# 4_Stepper_motor_control_board.net
KiCad netlist of a schematic drawn in EAGLE
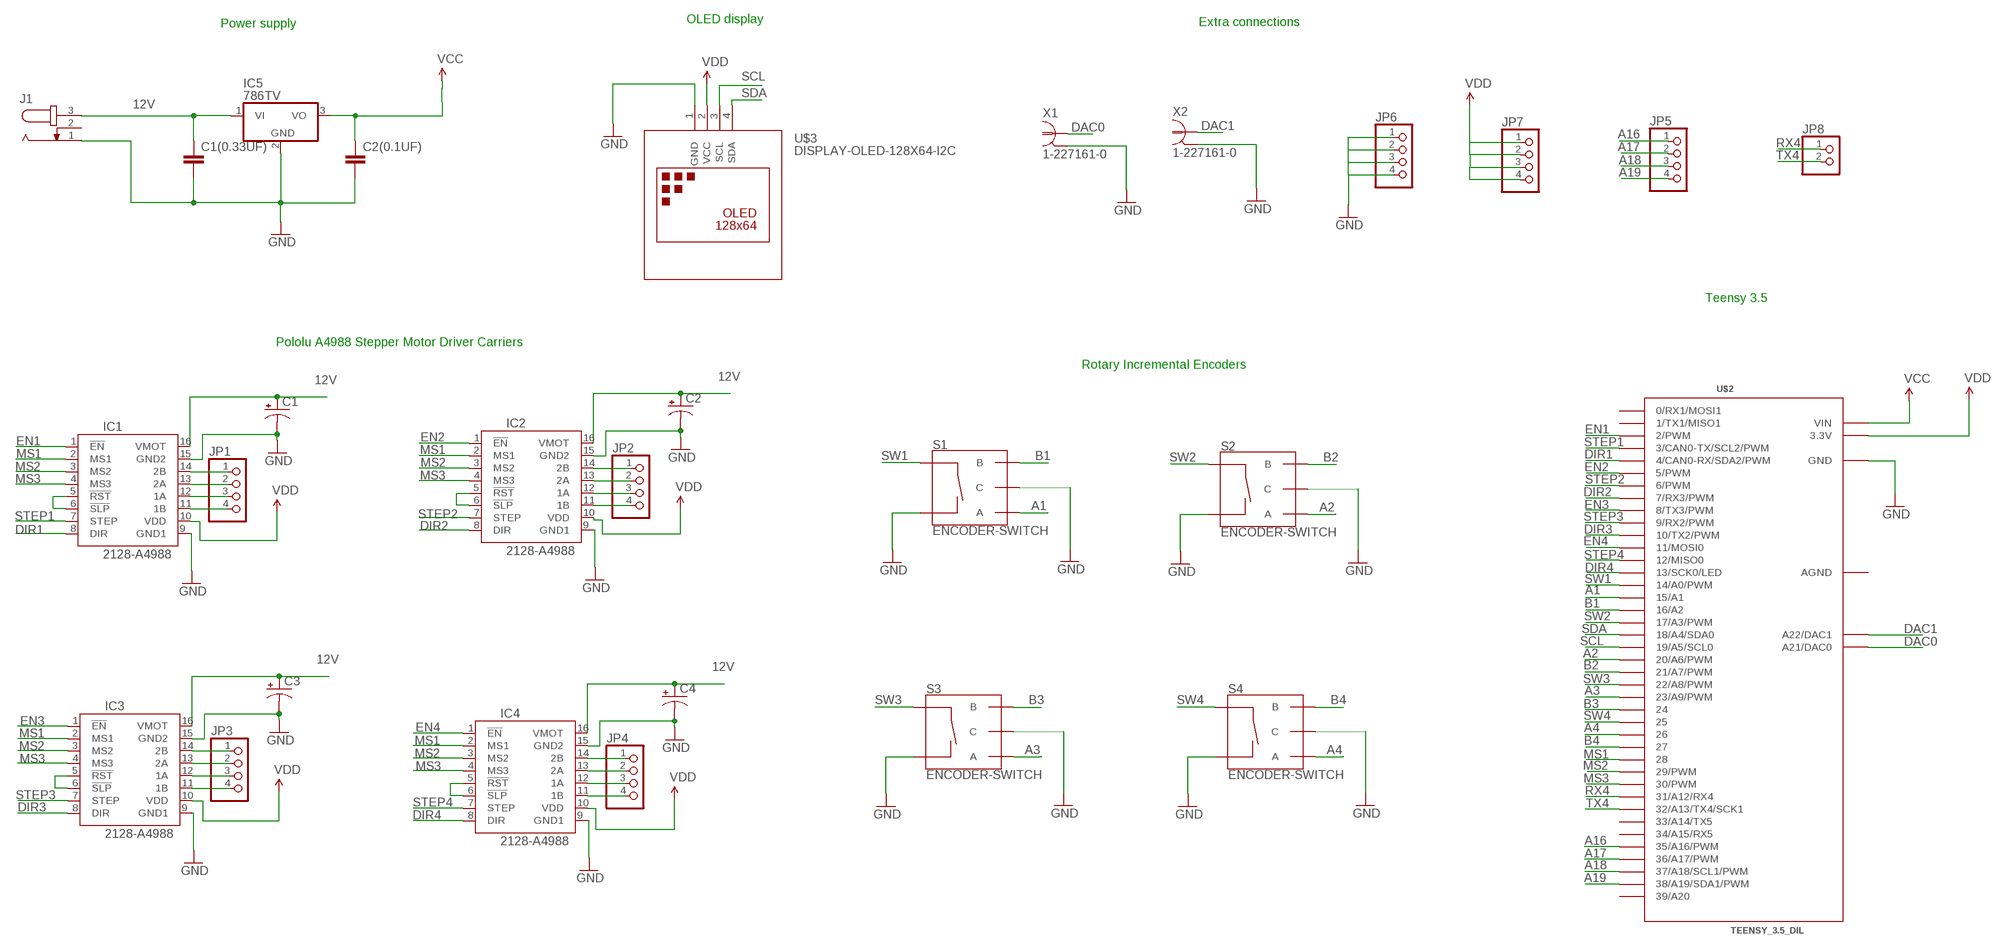
[diagram p0: schematic, sheet 1]

(export (version "E")
  (design (tool "Eeschema 10.0.6"))
  (components
    (comp (ref "C1")
      (value "CPOL-USE5-5")
      (footprint "eagle-import:E5-5")
      (libsource (lib "eagle-import") (part "CPOL-USE5-5"))
    )
    (comp (ref "C1(0.33UF)")
      (value "C2.5/4")
      (footprint "eagle-import:C2.5-4")
      (libsource (lib "eagle-import") (part "C2.5/4"))
    )
    (comp (ref "C2")
      (value "CPOL-USE5-5")
      (footprint "eagle-import:E5-5")
      (libsource (lib "eagle-import") (part "CPOL-USE5-5"))
    )
    (comp (ref "C2(0.1UF)")
      (value "C2.5/2")
      (footprint "eagle-import:C2.5-2")
      (libsource (lib "eagle-import") (part "C2.5/2"))
    )
    (comp (ref "C3")
      (value "CPOL-USE5-5")
      (footprint "eagle-import:E5-5")
      (libsource (lib "eagle-import") (part "CPOL-USE5-5"))
    )
    (comp (ref "C4")
      (value "CPOL-USE5-5")
      (footprint "eagle-import:E5-5")
      (libsource (lib "eagle-import") (part "CPOL-USE5-5"))
    )
    (comp (ref "IC1")
      (value "2128-A4988")
      (footprint "eagle-import:A4988")
      (libsource (lib "eagle-import") (part "2128-A4988"))
    )
    (comp (ref "IC2")
      (value "2128-A4988")
      (footprint "eagle-import:A4988")
      (libsource (lib "eagle-import") (part "2128-A4988"))
    )
    (comp (ref "IC3")
      (value "2128-A4988")
      (footprint "eagle-import:A4988")
      (libsource (lib "eagle-import") (part "2128-A4988"))
    )
    (comp (ref "IC4")
      (value "2128-A4988")
      (footprint "eagle-import:A4988")
      (libsource (lib "eagle-import") (part "2128-A4988"))
    )
    (comp (ref "IC5")
      (value "786TV")
      (footprint "eagle-import:TO220V")
      (libsource (lib "eagle-import") (part "78TV6"))
    )
    (comp (ref "J1")
      (value "JACK-PLUG0")
      (footprint "eagle-import:SPC4077")
      (libsource (lib "eagle-import") (part "JACK-PLUG0"))
    )
    (comp (ref "JP1")
      (value "PINHD-1X4")
      (footprint "eagle-import:1X04")
      (libsource (lib "eagle-import") (part "PINHD-1X4"))
    )
    (comp (ref "JP2")
      (value "PINHD-1X4")
      (footprint "eagle-import:1X04")
      (libsource (lib "eagle-import") (part "PINHD-1X4"))
    )
    (comp (ref "JP3")
      (value "PINHD-1X4")
      (footprint "eagle-import:1X04")
      (libsource (lib "eagle-import") (part "PINHD-1X4"))
    )
    (comp (ref "JP4")
      (value "PINHD-1X4")
      (footprint "eagle-import:1X04")
      (libsource (lib "eagle-import") (part "PINHD-1X4"))
    )
    (comp (ref "JP5")
      (value "PINHD-1X4")
      (footprint "eagle-import:1X04")
      (libsource (lib "eagle-import") (part "PINHD-1X4"))
    )
    (comp (ref "JP6")
      (value "PINHD-1X4")
      (footprint "eagle-import:1X04")
      (libsource (lib "eagle-import") (part "PINHD-1X4"))
    )
    (comp (ref "JP7")
      (value "PINHD-1X4")
      (footprint "eagle-import:1X04")
      (libsource (lib "eagle-import") (part "PINHD-1X4"))
    )
    (comp (ref "JP8")
      (value "PINHD-1X2")
      (footprint "eagle-import:1X02")
      (libsource (lib "eagle-import") (part "PINHD-1X2"))
    )
    (comp (ref "S1")
      (value "ENCODER-SWITCH")
      (footprint "eagle-import:ROTARY_ENC_PLAIN")
      (libsource (lib "eagle-import") (part "ENCODER-SWITCH"))
    )
    (comp (ref "S2")
      (value "ENCODER-SWITCH")
      (footprint "eagle-import:ROTARY_ENC_PLAIN")
      (libsource (lib "eagle-import") (part "ENCODER-SWITCH"))
    )
    (comp (ref "S3")
      (value "ENCODER-SWITCH")
      (footprint "eagle-import:ROTARY_ENC_PLAIN")
      (libsource (lib "eagle-import") (part "ENCODER-SWITCH"))
    )
    (comp (ref "S4")
      (value "ENCODER-SWITCH")
      (footprint "eagle-import:ROTARY_ENC_PLAIN")
      (libsource (lib "eagle-import") (part "ENCODER-SWITCH"))
    )
    (comp (ref "U$2")
      (value "TEENSY_3.5_DIL")
      (footprint "eagle-import:TEENSY_3.5_DIL")
      (libsource (lib "eagle-import") (part "TEENSY_3.5_DIL"))
    )
    (comp (ref "U$3")
      (value "DISPLAY-OLED-128X64-I2C")
      (footprint "eagle-import:DISPLAY-OLED-128X64-I2C")
      (libsource (lib "eagle-import") (part "DISPLAY-OLED-128X64-I2C"))
    )
    (comp (ref "X1")
      (value "1-227161-0")
      (footprint "eagle-import:AMP_227161")
      (fields (field (name "MF") "TYCO ELECTRONICS") (field (name "MPN") "1-227161"))
      (libsource (lib "eagle-import") (part "?2271611--0"))
    )
    (comp (ref "X2")
      (value "1-227161-0")
      (footprint "eagle-import:AMP_227161")
      (fields (field (name "MF") "TYCO ELECTRONICS") (field (name "MPN") "1-227161"))
      (libsource (lib "eagle-import") (part "?2271611--0"))
    )
  )
  (nets
    (net (code "1") (name "/12V") (class "Default")
      (node (ref "C1") (pin "+") (pinfunction "+_+") (pintype "passive"))
      (node (ref "C1(0.33UF)") (pin "1") (pinfunction "1_1") (pintype "passive"))
      (node (ref "C2") (pin "+") (pinfunction "+_+") (pintype "passive"))
      (node (ref "C3") (pin "+") (pinfunction "+_+") (pintype "passive"))
      (node (ref "C4") (pin "+") (pinfunction "+_+") (pintype "passive"))
      (node (ref "IC1") (pin "16") (pinfunction "VMOT_16") (pintype "power_in"))
      (node (ref "IC2") (pin "16") (pinfunction "VMOT_16") (pintype "power_in"))
      (node (ref "IC3") (pin "16") (pinfunction "VMOT_16") (pintype "power_in"))
      (node (ref "IC4") (pin "16") (pinfunction "VMOT_16") (pintype "power_in"))
      (node (ref "IC5") (pin "1") (pinfunction "VI_1") (pintype "input"))
      (node (ref "J1") (pin "3") (pinfunction "3_3") (pintype "passive"))
    )
    (net (code "2") (name "/A1") (class "Default")
      (node (ref "S1") (pin "A") (pinfunction "A_A") (pintype "bidirectional"))
      (node (ref "U$2") (pin "15/A1") (pinfunction "15/A1_15/A1") (pintype "bidirectional"))
    )
    (net (code "3") (name "/A2") (class "Default")
      (node (ref "S2") (pin "A") (pinfunction "A_A") (pintype "bidirectional"))
      (node (ref "U$2") (pin "20/A6") (pinfunction "20/A6/PWM_20/A6") (pintype "bidirectional"))
    )
    (net (code "4") (name "/A3") (class "Default")
      (node (ref "S3") (pin "A") (pinfunction "A_A") (pintype "bidirectional"))
      (node (ref "U$2") (pin "23/A9") (pinfunction "23/A9/PWM_23/A9") (pintype "bidirectional"))
    )
    (net (code "5") (name "/A4") (class "Default")
      (node (ref "S4") (pin "A") (pinfunction "A_A") (pintype "bidirectional"))
      (node (ref "U$2") (pin "26") (pinfunction "26_26") (pintype "bidirectional"))
    )
    (net (code "6") (name "/A16") (class "Default")
      (node (ref "JP5") (pin "1") (pinfunction "1_1") (pintype "passive"))
      (node (ref "U$2") (pin "35/A16") (pinfunction "35/A16/PWM_35/A16") (pintype "bidirectional"))
    )
    (net (code "7") (name "/A17") (class "Default")
      (node (ref "JP5") (pin "2") (pinfunction "2_2") (pintype "passive"))
      (node (ref "U$2") (pin "36/A17") (pinfunction "36/A17/PWM_36/A17") (pintype "bidirectional"))
    )
    (net (code "8") (name "/A18") (class "Default")
      (node (ref "JP5") (pin "3") (pinfunction "3_3") (pintype "passive"))
      (node (ref "U$2") (pin "37/A18") (pinfunction "37/A18/SCL1/PWM_37/A18") (pintype "bidirectional"))
    )
    (net (code "9") (name "/A19") (class "Default")
      (node (ref "JP5") (pin "4") (pinfunction "4_4") (pintype "passive"))
      (node (ref "U$2") (pin "38/A19") (pinfunction "38/A19/SDA1/PWM_38/A19") (pintype "bidirectional"))
    )
    (net (code "10") (name "/AGND") (class "Default")
      (node (ref "U$2") (pin "AGND") (pinfunction "AGND_AGND") (pintype "power_in"))
    )
    (net (code "11") (name "/B1") (class "Default")
      (node (ref "S1") (pin "B") (pinfunction "B_B") (pintype "bidirectional"))
      (node (ref "U$2") (pin "16/A2") (pinfunction "16/A2_16/A2") (pintype "bidirectional"))
    )
    (net (code "12") (name "/B2") (class "Default")
      (node (ref "S2") (pin "B") (pinfunction "B_B") (pintype "bidirectional"))
      (node (ref "U$2") (pin "21/A7") (pinfunction "21/A7/PWM_21/A7") (pintype "bidirectional"))
    )
    (net (code "13") (name "/B3") (class "Default")
      (node (ref "S3") (pin "B") (pinfunction "B_B") (pintype "bidirectional"))
      (node (ref "U$2") (pin "24") (pinfunction "24_24") (pintype "bidirectional"))
    )
    (net (code "14") (name "/B4") (class "Default")
      (node (ref "S4") (pin "B") (pinfunction "B_B") (pintype "bidirectional"))
      (node (ref "U$2") (pin "27") (pinfunction "27_27") (pintype "bidirectional"))
    )
    (net (code "15") (name "/DAC0") (class "Default")
      (node (ref "U$2") (pin "A21") (pinfunction "A21/DAC0_A21") (pintype "bidirectional"))
      (node (ref "X1") (pin "1") (pinfunction "1_1") (pintype "passive"))
    )
    (net (code "16") (name "/DAC1") (class "Default")
      (node (ref "U$2") (pin "A22") (pinfunction "A22/DAC1_A22") (pintype "bidirectional"))
      (node (ref "X2") (pin "1") (pinfunction "1_1") (pintype "passive"))
    )
    (net (code "17") (name "/DIR1") (class "Default")
      (node (ref "IC1") (pin "8") (pinfunction "DIR_8") (pintype "input"))
      (node (ref "U$2") (pin "4") (pinfunction "4/CAN0-RX/SDA2/PWM_4") (pintype "bidirectional"))
    )
    (net (code "18") (name "/DIR2") (class "Default")
      (node (ref "IC2") (pin "8") (pinfunction "DIR_8") (pintype "input"))
      (node (ref "U$2") (pin "7") (pinfunction "7/RX3/PWM_7") (pintype "bidirectional"))
    )
    (net (code "19") (name "/DIR3") (class "Default")
      (node (ref "IC3") (pin "8") (pinfunction "DIR_8") (pintype "input"))
      (node (ref "U$2") (pin "10") (pinfunction "10/TX2/PWM_10") (pintype "bidirectional"))
    )
    (net (code "20") (name "/DIR4") (class "Default")
      (node (ref "IC4") (pin "8") (pinfunction "DIR_8") (pintype "input"))
      (node (ref "U$2") (pin "13") (pinfunction "13/SCK0/LED_13") (pintype "bidirectional"))
    )
    (net (code "21") (name "/EN1") (class "Default")
      (node (ref "IC1") (pin "1") (pinfunction "~{EN}_1") (pintype "passive"))
      (node (ref "U$2") (pin "2") (pinfunction "2/PWM_2") (pintype "bidirectional"))
    )
    (net (code "22") (name "/EN2") (class "Default")
      (node (ref "IC2") (pin "1") (pinfunction "~{EN}_1") (pintype "passive"))
      (node (ref "U$2") (pin "5") (pinfunction "5/PWM_5") (pintype "bidirectional"))
    )
    (net (code "23") (name "/EN3") (class "Default")
      (node (ref "IC3") (pin "1") (pinfunction "~{EN}_1") (pintype "passive"))
      (node (ref "U$2") (pin "8") (pinfunction "8/TX3/PWM_8") (pintype "bidirectional"))
    )
    (net (code "24") (name "/EN4") (class "Default")
      (node (ref "IC4") (pin "1") (pinfunction "~{EN}_1") (pintype "passive"))
      (node (ref "U$2") (pin "11") (pinfunction "11/MOSI0_11") (pintype "bidirectional"))
    )
    (net (code "25") (name "/MS1") (class "Default")
      (node (ref "IC1") (pin "2") (pinfunction "MS1_2") (pintype "passive"))
      (node (ref "IC2") (pin "2") (pinfunction "MS1_2") (pintype "passive"))
      (node (ref "IC3") (pin "2") (pinfunction "MS1_2") (pintype "passive"))
      (node (ref "IC4") (pin "2") (pinfunction "MS1_2") (pintype "passive"))
      (node (ref "U$2") (pin "28") (pinfunction "28_28") (pintype "bidirectional"))
    )
    (net (code "26") (name "/MS2") (class "Default")
      (node (ref "IC1") (pin "3") (pinfunction "MS2_3") (pintype "passive"))
      (node (ref "IC2") (pin "3") (pinfunction "MS2_3") (pintype "passive"))
      (node (ref "IC3") (pin "3") (pinfunction "MS2_3") (pintype "passive"))
      (node (ref "IC4") (pin "3") (pinfunction "MS2_3") (pintype "passive"))
      (node (ref "U$2") (pin "29") (pinfunction "29/PWM_29") (pintype "bidirectional"))
    )
    (net (code "27") (name "/MS3") (class "Default")
      (node (ref "IC1") (pin "4") (pinfunction "MS3_4") (pintype "passive"))
      (node (ref "IC2") (pin "4") (pinfunction "MS3_4") (pintype "passive"))
      (node (ref "IC3") (pin "4") (pinfunction "MS3_4") (pintype "passive"))
      (node (ref "IC4") (pin "4") (pinfunction "MS3_4") (pintype "passive"))
      (node (ref "U$2") (pin "30") (pinfunction "30/PWM_30") (pintype "bidirectional"))
    )
    (net (code "28") (name "/RX4") (class "Default")
      (node (ref "JP8") (pin "1") (pinfunction "1_1") (pintype "passive"))
      (node (ref "U$2") (pin "31/A12") (pinfunction "31/A12/RX4_31/A12") (pintype "bidirectional"))
    )
    (net (code "29") (name "/SCL") (class "Default")
      (node (ref "U$2") (pin "19/A5") (pinfunction "19/A5/SCL0_19/A5") (pintype "bidirectional"))
      (node (ref "U$3") (pin "3") (pinfunction "SCL_3") (pintype "bidirectional"))
    )
    (net (code "30") (name "/SDA") (class "Default")
      (node (ref "U$2") (pin "18/A4") (pinfunction "18/A4/SDA0_18/A4") (pintype "bidirectional"))
      (node (ref "U$3") (pin "4") (pinfunction "SDA_4") (pintype "bidirectional"))
    )
    (net (code "31") (name "/STEP1") (class "Default")
      (node (ref "IC1") (pin "7") (pinfunction "STEP_7") (pintype "input"))
      (node (ref "U$2") (pin "3") (pinfunction "3/CAN0-TX/SCL2/PWM_3") (pintype "bidirectional"))
    )
    (net (code "32") (name "/STEP2") (class "Default")
      (node (ref "IC2") (pin "7") (pinfunction "STEP_7") (pintype "input"))
      (node (ref "U$2") (pin "6") (pinfunction "6/PWM_6") (pintype "bidirectional"))
    )
    (net (code "33") (name "/STEP3") (class "Default")
      (node (ref "IC3") (pin "7") (pinfunction "STEP_7") (pintype "input"))
      (node (ref "U$2") (pin "9") (pinfunction "9/RX2/PWM_9") (pintype "bidirectional"))
    )
    (net (code "34") (name "/STEP4") (class "Default")
      (node (ref "IC4") (pin "7") (pinfunction "STEP_7") (pintype "input"))
      (node (ref "U$2") (pin "12") (pinfunction "12/MISO0_12") (pintype "bidirectional"))
    )
    (net (code "35") (name "/SW1") (class "Default")
      (node (ref "S1") (pin "SW+") (pinfunction "SW+_SW+") (pintype "bidirectional"))
      (node (ref "U$2") (pin "14/A0") (pinfunction "14/A0/PWM_14/A0") (pintype "bidirectional"))
    )
    (net (code "36") (name "/SW2") (class "Default")
      (node (ref "S2") (pin "SW+") (pinfunction "SW+_SW+") (pintype "bidirectional"))
      (node (ref "U$2") (pin "17/A3") (pinfunction "17/A3/PWM_17/A3") (pintype "bidirectional"))
    )
    (net (code "37") (name "/SW3") (class "Default")
      (node (ref "S3") (pin "SW+") (pinfunction "SW+_SW+") (pintype "bidirectional"))
      (node (ref "U$2") (pin "22/A8") (pinfunction "22/A8/PWM_22/A8") (pintype "bidirectional"))
    )
    (net (code "38") (name "/SW4") (class "Default")
      (node (ref "S4") (pin "SW+") (pinfunction "SW+_SW+") (pintype "bidirectional"))
      (node (ref "U$2") (pin "25") (pinfunction "25_25") (pintype "bidirectional"))
    )
    (net (code "39") (name "/TX4") (class "Default")
      (node (ref "JP8") (pin "2") (pinfunction "2_2") (pintype "passive"))
      (node (ref "U$2") (pin "32/A13") (pinfunction "32/A13/TX4/SCK1_32/A13") (pintype "bidirectional"))
    )
    (net (code "40") (name "GND") (class "Default")
      (node (ref "C1") (pin "-") (pinfunction "-_-") (pintype "passive"))
      (node (ref "C1(0.33UF)") (pin "2") (pinfunction "2_2") (pintype "passive"))
      (node (ref "C2") (pin "-") (pinfunction "-_-") (pintype "passive"))
      (node (ref "C2(0.1UF)") (pin "2") (pinfunction "2_2") (pintype "passive"))
      (node (ref "C3") (pin "-") (pinfunction "-_-") (pintype "passive"))
      (node (ref "C4") (pin "-") (pinfunction "-_-") (pintype "passive"))
      (node (ref "IC1") (pin "15") (pinfunction "GND2_15") (pintype "power_in"))
      (node (ref "IC1") (pin "9") (pinfunction "GND1_9") (pintype "power_in"))
      (node (ref "IC2") (pin "15") (pinfunction "GND2_15") (pintype "power_in"))
      (node (ref "IC2") (pin "9") (pinfunction "GND1_9") (pintype "power_in"))
      (node (ref "IC3") (pin "15") (pinfunction "GND2_15") (pintype "power_in"))
      (node (ref "IC3") (pin "9") (pinfunction "GND1_9") (pintype "power_in"))
      (node (ref "IC4") (pin "15") (pinfunction "GND2_15") (pintype "power_in"))
      (node (ref "IC4") (pin "9") (pinfunction "GND1_9") (pintype "power_in"))
      (node (ref "IC5") (pin "2") (pinfunction "GND_2") (pintype "passive"))
      (node (ref "J1") (pin "1") (pinfunction "1_1") (pintype "passive"))
      (node (ref "JP6") (pin "1") (pinfunction "1_1") (pintype "passive"))
      (node (ref "JP6") (pin "2") (pinfunction "2_2") (pintype "passive"))
      (node (ref "JP6") (pin "3") (pinfunction "3_3") (pintype "passive"))
      (node (ref "JP6") (pin "4") (pinfunction "4_4") (pintype "passive"))
      (node (ref "S1") (pin "C") (pinfunction "C_C") (pintype "bidirectional"))
      (node (ref "S1") (pin "SW-") (pinfunction "SW-_SW-") (pintype "bidirectional"))
      (node (ref "S2") (pin "C") (pinfunction "C_C") (pintype "bidirectional"))
      (node (ref "S2") (pin "SW-") (pinfunction "SW-_SW-") (pintype "bidirectional"))
      (node (ref "S3") (pin "C") (pinfunction "C_C") (pintype "bidirectional"))
      (node (ref "S3") (pin "SW-") (pinfunction "SW-_SW-") (pintype "bidirectional"))
      (node (ref "S4") (pin "C") (pinfunction "C_C") (pintype "bidirectional"))
      (node (ref "S4") (pin "SW-") (pinfunction "SW-_SW-") (pintype "bidirectional"))
      (node (ref "U$2") (pin "GND") (pinfunction "GND_GND") (pintype "power_in"))
      (node (ref "U$2") (pin "GND1") (pinfunction "GND_GND1") (pintype "power_in"))
      (node (ref "U$3") (pin "1") (pinfunction "GND_1") (pintype "power_in"))
      (node (ref "X1") (pin "2") (pinfunction "2_2") (pintype "passive"))
      (node (ref "X2") (pin "2") (pinfunction "2_2") (pintype "passive"))
    )
    (net (code "41") (name "Net-(IC1-1A)") (class "Default")
      (node (ref "IC1") (pin "12") (pinfunction "1A_12") (pintype "output"))
      (node (ref "JP1") (pin "3") (pinfunction "3_3") (pintype "passive"))
    )
    (net (code "42") (name "Net-(IC1-1B)") (class "Default")
      (node (ref "IC1") (pin "11") (pinfunction "1B_11") (pintype "output"))
      (node (ref "JP1") (pin "4") (pinfunction "4_4") (pintype "passive"))
    )
    (net (code "43") (name "Net-(IC1-2A)") (class "Default")
      (node (ref "IC1") (pin "13") (pinfunction "2A_13") (pintype "output"))
      (node (ref "JP1") (pin "2") (pinfunction "2_2") (pintype "passive"))
    )
    (net (code "44") (name "Net-(IC1-2B)") (class "Default")
      (node (ref "IC1") (pin "14") (pinfunction "2B_14") (pintype "output"))
      (node (ref "JP1") (pin "1") (pinfunction "1_1") (pintype "passive"))
    )
    (net (code "45") (name "Net-(IC1-~{RST})") (class "Default")
      (node (ref "IC1") (pin "5") (pinfunction "~{RST}_5") (pintype "passive"))
      (node (ref "IC1") (pin "6") (pinfunction "~{SLP}_6") (pintype "passive"))
    )
    (net (code "46") (name "Net-(IC2-1A)") (class "Default")
      (node (ref "IC2") (pin "12") (pinfunction "1A_12") (pintype "output"))
      (node (ref "JP2") (pin "3") (pinfunction "3_3") (pintype "passive"))
    )
    (net (code "47") (name "Net-(IC2-1B)") (class "Default")
      (node (ref "IC2") (pin "11") (pinfunction "1B_11") (pintype "output"))
      (node (ref "JP2") (pin "4") (pinfunction "4_4") (pintype "passive"))
    )
    (net (code "48") (name "Net-(IC2-2A)") (class "Default")
      (node (ref "IC2") (pin "13") (pinfunction "2A_13") (pintype "output"))
      (node (ref "JP2") (pin "2") (pinfunction "2_2") (pintype "passive"))
    )
    (net (code "49") (name "Net-(IC2-2B)") (class "Default")
      (node (ref "IC2") (pin "14") (pinfunction "2B_14") (pintype "output"))
      (node (ref "JP2") (pin "1") (pinfunction "1_1") (pintype "passive"))
    )
    (net (code "50") (name "Net-(IC2-~{RST})") (class "Default")
      (node (ref "IC2") (pin "5") (pinfunction "~{RST}_5") (pintype "passive"))
      (node (ref "IC2") (pin "6") (pinfunction "~{SLP}_6") (pintype "passive"))
    )
    (net (code "51") (name "Net-(IC3-1A)") (class "Default")
      (node (ref "IC3") (pin "12") (pinfunction "1A_12") (pintype "output"))
      (node (ref "JP3") (pin "3") (pinfunction "3_3") (pintype "passive"))
    )
    (net (code "52") (name "Net-(IC3-1B)") (class "Default")
      (node (ref "IC3") (pin "11") (pinfunction "1B_11") (pintype "output"))
      (node (ref "JP3") (pin "4") (pinfunction "4_4") (pintype "passive"))
    )
    (net (code "53") (name "Net-(IC3-2A)") (class "Default")
      (node (ref "IC3") (pin "13") (pinfunction "2A_13") (pintype "output"))
      (node (ref "JP3") (pin "2") (pinfunction "2_2") (pintype "passive"))
    )
    (net (code "54") (name "Net-(IC3-2B)") (class "Default")
      (node (ref "IC3") (pin "14") (pinfunction "2B_14") (pintype "output"))
      (node (ref "JP3") (pin "1") (pinfunction "1_1") (pintype "passive"))
    )
    (net (code "55") (name "Net-(IC3-~{RST})") (class "Default")
      (node (ref "IC3") (pin "5") (pinfunction "~{RST}_5") (pintype "passive"))
      (node (ref "IC3") (pin "6") (pinfunction "~{SLP}_6") (pintype "passive"))
    )
    (net (code "56") (name "Net-(IC4-1A)") (class "Default")
      (node (ref "IC4") (pin "12") (pinfunction "1A_12") (pintype "output"))
      (node (ref "JP4") (pin "3") (pinfunction "3_3") (pintype "passive"))
    )
    (net (code "57") (name "Net-(IC4-1B)") (class "Default")
      (node (ref "IC4") (pin "11") (pinfunction "1B_11") (pintype "output"))
      (node (ref "JP4") (pin "4") (pinfunction "4_4") (pintype "passive"))
    )
    (net (code "58") (name "Net-(IC4-2A)") (class "Default")
      (node (ref "IC4") (pin "13") (pinfunction "2A_13") (pintype "output"))
      (node (ref "JP4") (pin "2") (pinfunction "2_2") (pintype "passive"))
    )
    (net (code "59") (name "Net-(IC4-2B)") (class "Default")
      (node (ref "IC4") (pin "14") (pinfunction "2B_14") (pintype "output"))
      (node (ref "JP4") (pin "1") (pinfunction "1_1") (pintype "passive"))
    )
    (net (code "60") (name "Net-(IC4-~{RST})") (class "Default")
      (node (ref "IC4") (pin "5") (pinfunction "~{RST}_5") (pintype "passive"))
      (node (ref "IC4") (pin "6") (pinfunction "~{SLP}_6") (pintype "passive"))
    )
    (net (code "61") (name "VCC") (class "Default")
      (node (ref "C2(0.1UF)") (pin "1") (pinfunction "1_1") (pintype "passive"))
      (node (ref "IC5") (pin "3") (pinfunction "VO_3") (pintype "passive"))
      (node (ref "U$2") (pin "VIN") (pinfunction "VIN_VIN") (pintype "power_in"))
    )
    (net (code "62") (name "VDD") (class "Default")
      (node (ref "IC1") (pin "10") (pinfunction "VDD_10") (pintype "power_in"))
      (node (ref "IC2") (pin "10") (pinfunction "VDD_10") (pintype "power_in"))
      (node (ref "IC3") (pin "10") (pinfunction "VDD_10") (pintype "power_in"))
      (node (ref "IC4") (pin "10") (pinfunction "VDD_10") (pintype "power_in"))
      (node (ref "JP7") (pin "1") (pinfunction "1_1") (pintype "passive"))
      (node (ref "JP7") (pin "2") (pinfunction "2_2") (pintype "passive"))
      (node (ref "JP7") (pin "3") (pinfunction "3_3") (pintype "passive"))
      (node (ref "JP7") (pin "4") (pinfunction "4_4") (pintype "passive"))
      (node (ref "U$2") (pin "3.3V") (pinfunction "3.3V_3.3V") (pintype "power_in"))
      (node (ref "U$2") (pin "3.3V3") (pinfunction "3.3V_3.3V3") (pintype "power_in"))
      (node (ref "U$3") (pin "2") (pinfunction "VCC_2") (pintype "power_in"))
    )
    (net (code "63") (name "unconnected-(J1-Pad2)") (class "Default")
      (node (ref "J1") (pin "2") (pinfunction "2_2") (pintype "passive"))
    )
    (net (code "64") (name "unconnected-(U$2-0{slash}RX1{slash}MOSI1-Pad0)") (class "Default")
      (node (ref "U$2") (pin "0") (pinfunction "0/RX1/MOSI1_0") (pintype "bidirectional"))
    )
    (net (code "65") (name "unconnected-(U$2-1{slash}TX1{slash}MISO1-Pad1)") (class "Default")
      (node (ref "U$2") (pin "1") (pinfunction "1/TX1/MISO1_1") (pintype "bidirectional"))
    )
    (net (code "66") (name "unconnected-(U$2-33{slash}A14{slash}TX5-Pad33{slash}A14)") (class "Default")
      (node (ref "U$2") (pin "33/A14") (pinfunction "33/A14/TX5_33/A14") (pintype "bidirectional"))
    )
    (net (code "67") (name "unconnected-(U$2-34{slash}A15{slash}RX5-Pad34{slash}A15)") (class "Default")
      (node (ref "U$2") (pin "34/A15") (pinfunction "34/A15/RX5_34/A15") (pintype "bidirectional"))
    )
    (net (code "68") (name "unconnected-(U$2-Pad39{slash}A20)") (class "Default")
      (node (ref "U$2") (pin "39/A20") (pinfunction "39/A20_39/A20") (pintype "bidirectional"))
    )
  )
)
